# plant-monitor.net
KiCad netlist of a schematic drawn in EAGLE
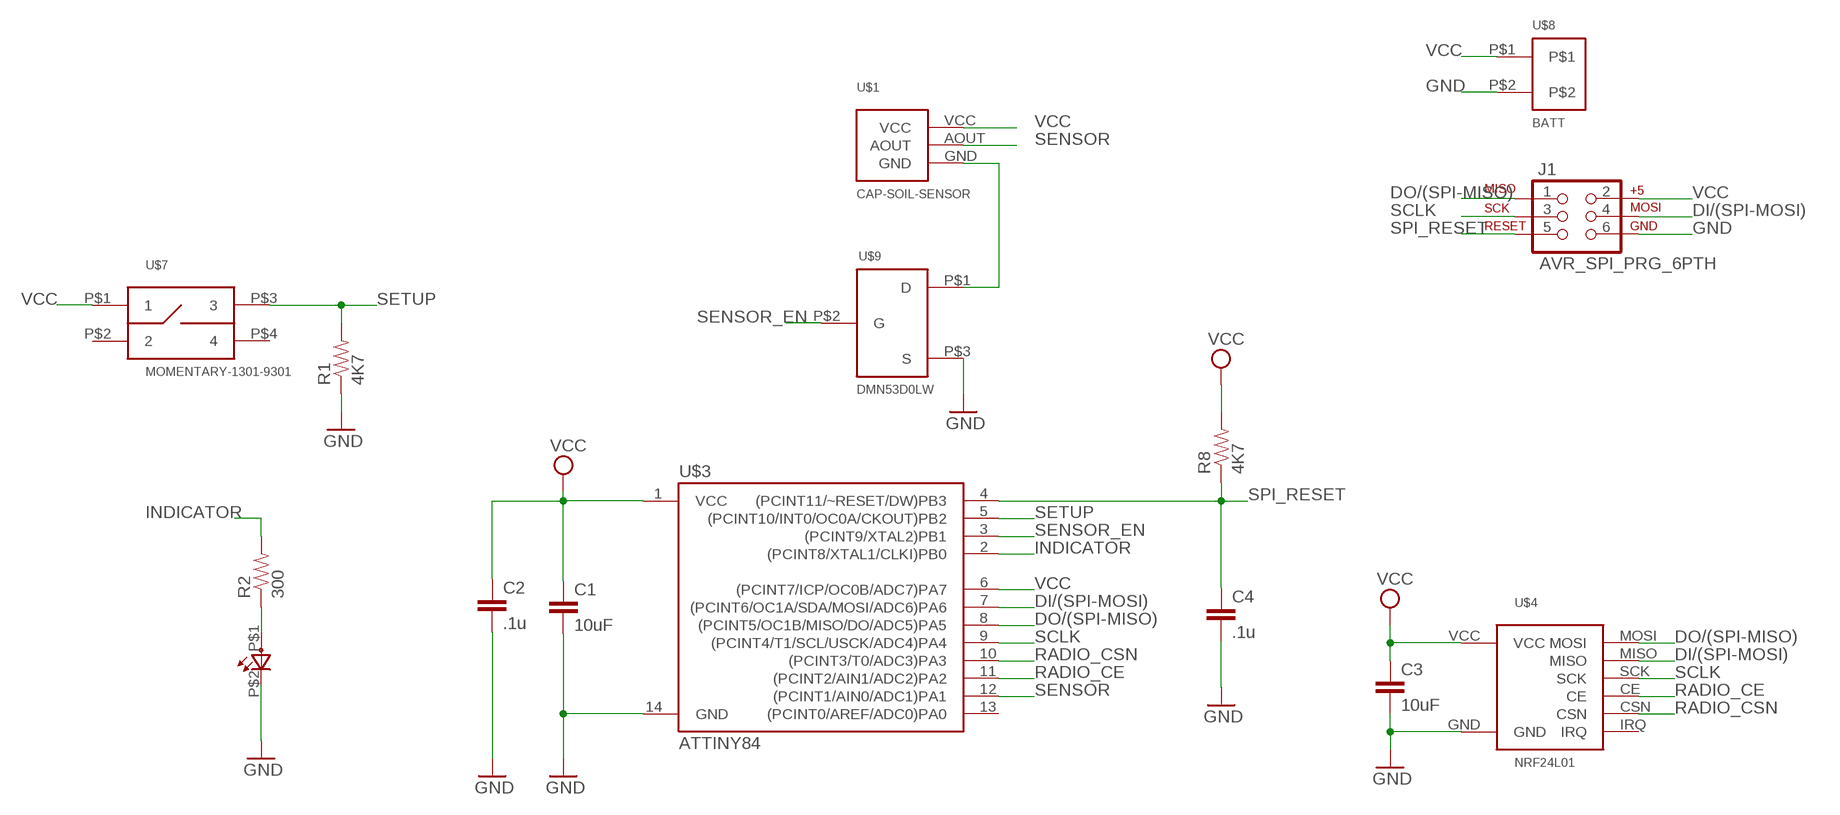
[diagram p0: schematic, sheet 1]

(export (version "E")
  (design (tool "Eeschema 10.0.6"))
  (components
    (comp (ref "C1")
      (value "10uF")
      (footprint "eagle-import:1206")
      (libsource (lib "eagle-import") (part "10UF-1206-6.3V-20%"))
    )
    (comp (ref "C2")
      (value ".1u")
      (footprint "eagle-import:0805")
      (libsource (lib "eagle-import") (part "CAP0805"))
    )
    (comp (ref "C3")
      (value "10uF")
      (footprint "eagle-import:1206")
      (libsource (lib "eagle-import") (part "10UF-1206-6.3V-20%"))
    )
    (comp (ref "C4")
      (value ".1u")
      (footprint "eagle-import:0805")
      (libsource (lib "eagle-import") (part "CAP0805"))
    )
    (comp (ref "J1")
      (value "AVR_SPI_PRG_6PTH")
      (footprint "eagle-import:2X3")
      (libsource (lib "eagle-import") (part "AVR_SPI_PRG_6PTH"))
    )
    (comp (ref "R1")
      (value "4K7")
      (footprint "eagle-import:0805")
      (libsource (lib "eagle-import") (part "RESISTOR"))
    )
    (comp (ref "R2")
      (value "300")
      (footprint "eagle-import:0805")
      (libsource (lib "eagle-import") (part "RESISTOR"))
    )
    (comp (ref "R8")
      (value "4K7")
      (footprint "eagle-import:0805")
      (libsource (lib "eagle-import") (part "RESISTOR"))
    )
    (comp (ref "U$1")
      (value "CAP-SOIL-SENSOR")
      (footprint "eagle-import:CAP-SOIL-SENSOR")
      (libsource (lib "eagle-import") (part "CAP-SOIL-SENSOR"))
    )
    (comp (ref "U$3")
      (value "ATTINY84")
      (footprint "eagle-import:SO14")
      (libsource (lib "eagle-import") (part "ATTINY84"))
    )
    (comp (ref "U$4")
      (value "NRF24L01")
      (footprint "eagle-import:NRF24L01")
      (libsource (lib "eagle-import") (part "NRF24L01"))
    )
    (comp (ref "U$6")
      (value "LED")
      (footprint "eagle-import:0805")
      (libsource (lib "eagle-import") (part "LED"))
    )
    (comp (ref "U$7")
      (value "MOMENTARY-1301-9301")
      (footprint "eagle-import:MOMENTARY-1301")
      (libsource (lib "eagle-import") (part "MOMENTARY-1301-9301"))
    )
    (comp (ref "U$8")
      (value "BATT")
      (footprint "eagle-import:JST-PH-2")
      (libsource (lib "eagle-import") (part "JST-PH-2"))
    )
    (comp (ref "U$9")
      (value "DMN53D0LW")
      (footprint "eagle-import:SOT-323")
      (libsource (lib "eagle-import") (part "DMN53D0LW"))
    )
  )
  (nets
    (net (code "1") (name "/DI{slash}(SPI-MOSI)") (class "Default")
      (node (ref "J1") (pin "4") (pinfunction "4_4") (pintype "passive"))
      (node (ref "U$3") (pin "7") (pinfunction "(PCINT6/OC1A/SDA/MOSI/ADC6)PA6_7") (pintype "bidirectional"))
      (node (ref "U$4") (pin "MISO") (pinfunction "MISO_MISO") (pintype "bidirectional"))
    )
    (net (code "2") (name "/DO{slash}(SPI-MISO)") (class "Default")
      (node (ref "J1") (pin "1") (pinfunction "1_1") (pintype "passive"))
      (node (ref "U$3") (pin "8") (pinfunction "(PCINT5/OC1B/MISO/DO/ADC5)PA5_8") (pintype "bidirectional"))
      (node (ref "U$4") (pin "MOSI") (pinfunction "MOSI_MOSI") (pintype "bidirectional"))
    )
    (net (code "3") (name "/INDICATOR") (class "Default")
      (node (ref "R2") (pin "2") (pinfunction "2_2") (pintype "passive"))
      (node (ref "U$3") (pin "2") (pinfunction "(PCINT8/XTAL1/CLKI)PB0_2") (pintype "bidirectional"))
    )
    (net (code "4") (name "/RADIO_CE") (class "Default")
      (node (ref "U$3") (pin "11") (pinfunction "(PCINT2/AIN1/ADC2)PA2_11") (pintype "bidirectional"))
      (node (ref "U$4") (pin "CE") (pinfunction "CE_CE") (pintype "bidirectional"))
    )
    (net (code "5") (name "/RADIO_CSN") (class "Default")
      (node (ref "U$3") (pin "10") (pinfunction "(PCINT3/T0/ADC3)PA3_10") (pintype "bidirectional"))
      (node (ref "U$4") (pin "CSN") (pinfunction "CSN_CSN") (pintype "bidirectional"))
    )
    (net (code "6") (name "/SCLK") (class "Default")
      (node (ref "J1") (pin "3") (pinfunction "3_3") (pintype "passive"))
      (node (ref "U$3") (pin "9") (pinfunction "(PCINT4/T1/SCL/USCK/ADC4)PA4_9") (pintype "bidirectional"))
      (node (ref "U$4") (pin "SCK") (pinfunction "SCK_SCK") (pintype "bidirectional"))
    )
    (net (code "7") (name "/SENSOR") (class "Default")
      (node (ref "U$1") (pin "AOUT") (pinfunction "AOUT_AOUT") (pintype "output"))
      (node (ref "U$3") (pin "12") (pinfunction "(PCINT1/AIN0/ADC1)PA1_12") (pintype "bidirectional"))
    )
    (net (code "8") (name "/SENSOR_EN") (class "Default")
      (node (ref "U$3") (pin "3") (pinfunction "(PCINT9/XTAL2)PB1_3") (pintype "bidirectional"))
      (node (ref "U$9") (pin "P$2") (pinfunction "G_P$2") (pintype "bidirectional"))
    )
    (net (code "9") (name "/SETUP") (class "Default")
      (node (ref "R1") (pin "2") (pinfunction "2_2") (pintype "passive"))
      (node (ref "U$3") (pin "5") (pinfunction "(PCINT10/INT0/OC0A/CKOUT)PB2_5") (pintype "bidirectional"))
      (node (ref "U$7") (pin "P$3") (pinfunction "3_P$3") (pintype "input"))
    )
    (net (code "10") (name "/SPI_RESET") (class "Default")
      (node (ref "C4") (pin "1") (pinfunction "1_1") (pintype "passive"))
      (node (ref "J1") (pin "5") (pinfunction "5_5") (pintype "passive"))
      (node (ref "R8") (pin "1") (pinfunction "1_1") (pintype "passive"))
      (node (ref "U$3") (pin "4") (pinfunction "(PCINT11/~{RESET/DW})PB3_4") (pintype "bidirectional"))
    )
    (net (code "11") (name "GND") (class "Default")
      (node (ref "C1") (pin "2") (pinfunction "2_2") (pintype "passive"))
      (node (ref "C2") (pin "2") (pinfunction "2_2") (pintype "passive"))
      (node (ref "C3") (pin "2") (pinfunction "2_2") (pintype "passive"))
      (node (ref "C4") (pin "2") (pinfunction "2_2") (pintype "passive"))
      (node (ref "J1") (pin "6") (pinfunction "6_6") (pintype "passive"))
      (node (ref "R1") (pin "1") (pinfunction "1_1") (pintype "passive"))
      (node (ref "U$3") (pin "14") (pinfunction "GND_14") (pintype "bidirectional"))
      (node (ref "U$4") (pin "GND") (pinfunction "GND_GND") (pintype "power_in"))
      (node (ref "U$6") (pin "P$2") (pinfunction "C_P$2") (pintype "passive"))
      (node (ref "U$8") (pin "P$2") (pinfunction "P$2_P$2") (pintype "bidirectional"))
      (node (ref "U$9") (pin "P$3") (pinfunction "S_P$3") (pintype "bidirectional"))
    )
    (net (code "12") (name "Net-(U$6-A)") (class "Default")
      (node (ref "R2") (pin "1") (pinfunction "1_1") (pintype "passive"))
      (node (ref "U$6") (pin "P$1") (pinfunction "A_P$1") (pintype "passive"))
    )
    (net (code "13") (name "Net-(U$9-D)") (class "Default")
      (node (ref "U$1") (pin "GND") (pinfunction "GND_GND") (pintype "power_in"))
      (node (ref "U$9") (pin "P$1") (pinfunction "D_P$1") (pintype "bidirectional"))
    )
    (net (code "14") (name "VCC") (class "Default")
      (node (ref "C1") (pin "1") (pinfunction "1_1") (pintype "passive"))
      (node (ref "C2") (pin "1") (pinfunction "1_1") (pintype "passive"))
      (node (ref "C3") (pin "1") (pinfunction "1_1") (pintype "passive"))
      (node (ref "J1") (pin "2") (pinfunction "2_2") (pintype "passive"))
      (node (ref "R8") (pin "2") (pinfunction "2_2") (pintype "passive"))
      (node (ref "U$1") (pin "VCC") (pinfunction "VCC_VCC") (pintype "power_in"))
      (node (ref "U$3") (pin "1") (pinfunction "VCC_1") (pintype "bidirectional"))
      (node (ref "U$3") (pin "6") (pinfunction "(PCINT7/ICP/OC0B/ADC7)PA7_6") (pintype "bidirectional"))
      (node (ref "U$4") (pin "VCC") (pinfunction "VCC_VCC") (pintype "power_in"))
      (node (ref "U$7") (pin "P$1") (pinfunction "1_P$1") (pintype "input"))
      (node (ref "U$8") (pin "P$1") (pinfunction "P$1_P$1") (pintype "bidirectional"))
    )
    (net (code "15") (name "unconnected-(U$3-(PCINT0{slash}AREF{slash}ADC0)PA0-Pad13)") (class "Default")
      (node (ref "U$3") (pin "13") (pinfunction "(PCINT0/AREF/ADC0)PA0_13") (pintype "bidirectional"))
    )
    (net (code "16") (name "unconnected-(U$4-PadIRQ)") (class "Default")
      (node (ref "U$4") (pin "IRQ") (pinfunction "IRQ_IRQ") (pintype "bidirectional"))
    )
    (net (code "17") (name "unconnected-(U$7-2-PadP$2)") (class "Default")
      (node (ref "U$7") (pin "P$2") (pinfunction "2_P$2") (pintype "input"))
    )
    (net (code "18") (name "unconnected-(U$7-4-PadP$4)") (class "Default")
      (node (ref "U$7") (pin "P$4") (pinfunction "4_P$4") (pintype "input"))
    )
  )
)
